# espstack.net
KiCad netlist of a schematic drawn in EAGLE
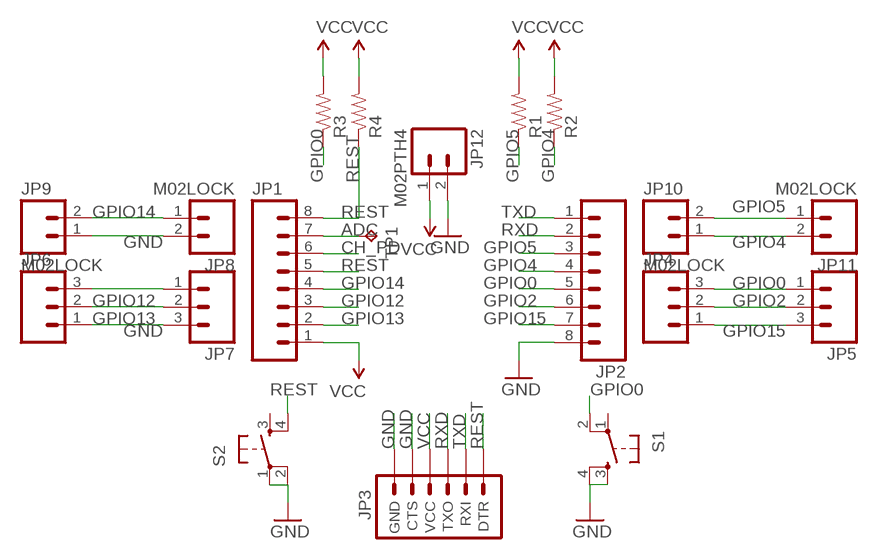
[diagram p0: schematic, sheet 1]

(export (version "E")
  (design (tool "Eeschema 10.0.6"))
  (components
    (comp (ref "JP1")
      (value "M08LOCK_LONGPADS")
      (footprint "eagle-import:1X08_LOCK_LONGPADS")
      (libsource (lib "eagle-import") (part "M08LOCK_LONGPADS"))
    )
    (comp (ref "JP2")
      (value "M08LOCK_LONGPADS")
      (footprint "eagle-import:1X08_LOCK_LONGPADS")
      (libsource (lib "eagle-import") (part "M08LOCK_LONGPADS"))
    )
    (comp (ref "JP3")
      (value "ARDUINO_SERIAL_PROGRAMLOCK")
      (footprint "eagle-import:1X06_LOCK")
      (libsource (lib "eagle-import") (part "ARDUINO_SERIAL_PROGRAMLOCK"))
    )
    (comp (ref "JP4")
      (value "M03LOCK")
      (footprint "eagle-import:1X03_LOCK")
      (libsource (lib "eagle-import") (part "M03LOCK"))
    )
    (comp (ref "JP5")
      (value "M03LOCK")
      (footprint "eagle-import:1X03_LOCK")
      (libsource (lib "eagle-import") (part "M03LOCK"))
    )
    (comp (ref "JP6")
      (value "M03LOCK")
      (footprint "eagle-import:1X03_LOCK")
      (libsource (lib "eagle-import") (part "M03LOCK"))
    )
    (comp (ref "JP7")
      (value "M03LOCK")
      (footprint "eagle-import:1X03_LOCK")
      (libsource (lib "eagle-import") (part "M03LOCK"))
    )
    (comp (ref "JP8")
      (value "M02LOCK")
      (footprint "eagle-import:1X02_LOCK")
      (libsource (lib "eagle-import") (part "M02LOCK"))
    )
    (comp (ref "JP9")
      (value "M02LOCK")
      (footprint "eagle-import:1X02_LOCK")
      (libsource (lib "eagle-import") (part "M02LOCK"))
    )
    (comp (ref "JP10")
      (value "M02LOCK")
      (footprint "eagle-import:1X02_LOCK")
      (libsource (lib "eagle-import") (part "M02LOCK"))
    )
    (comp (ref "JP11")
      (value "M02LOCK")
      (footprint "eagle-import:1X02_LOCK")
      (libsource (lib "eagle-import") (part "M02LOCK"))
    )
    (comp (ref "JP12")
      (value "M02PTH4")
      (footprint "eagle-import:1X02_XTRA_BIG")
      (libsource (lib "eagle-import") (part "M02PTH4"))
    )
    (comp (ref "R1")
      (value "RESISTOR0805-RES")
      (footprint "eagle-import:0805")
      (libsource (lib "eagle-import") (part "RESISTOR0805-RES"))
    )
    (comp (ref "R2")
      (value "RESISTOR0805-RES")
      (footprint "eagle-import:0805")
      (libsource (lib "eagle-import") (part "RESISTOR0805-RES"))
    )
    (comp (ref "R3")
      (value "RESISTOR0805-RES")
      (footprint "eagle-import:0805")
      (libsource (lib "eagle-import") (part "RESISTOR0805-RES"))
    )
    (comp (ref "R4")
      (value "RESISTOR0805-RES")
      (footprint "eagle-import:0805")
      (libsource (lib "eagle-import") (part "RESISTOR0805-RES"))
    )
    (comp (ref "S1")
      (value "TAC_SWITCHPTH")
      (footprint "eagle-import:TACTILE-PTH")
      (libsource (lib "eagle-import") (part "TAC_SWITCHPTH"))
    )
    (comp (ref "S2")
      (value "TAC_SWITCHPTH")
      (footprint "eagle-import:TACTILE-PTH")
      (libsource (lib "eagle-import") (part "TAC_SWITCHPTH"))
    )
    (comp (ref "TP1")
      (value "TPB2,54")
      (footprint "eagle-import:B2,54")
      (libsource (lib "eagle-import") (part "TPB2,54"))
    )
  )
  (nets
    (net (code "1") (name "/ADC") (class "Default")
      (node (ref "JP1") (pin "7") (pinfunction "7_7") (pintype "passive"))
      (node (ref "TP1") (pin "TP") (pinfunction "TP_TP") (pintype "input"))
    )
    (net (code "2") (name "/CH_PD") (class "Default")
      (node (ref "JP1") (pin "6") (pinfunction "6_6") (pintype "passive"))
    )
    (net (code "3") (name "/GPIO0") (class "Default")
      (node (ref "JP2") (pin "5") (pinfunction "5_5") (pintype "passive"))
      (node (ref "JP4") (pin "3") (pinfunction "3_3") (pintype "passive"))
      (node (ref "JP5") (pin "1") (pinfunction "1_1") (pintype "passive"))
      (node (ref "R3") (pin "1") (pinfunction "1_1") (pintype "passive"))
      (node (ref "S1") (pin "2") (pinfunction "2_2") (pintype "passive"))
    )
    (net (code "4") (name "/GPIO2") (class "Default")
      (node (ref "JP2") (pin "6") (pinfunction "6_6") (pintype "passive"))
      (node (ref "JP4") (pin "2") (pinfunction "2_2") (pintype "passive"))
      (node (ref "JP5") (pin "2") (pinfunction "2_2") (pintype "passive"))
    )
    (net (code "5") (name "/GPIO4") (class "Default")
      (node (ref "JP10") (pin "1") (pinfunction "1_1") (pintype "passive"))
      (node (ref "JP11") (pin "2") (pinfunction "2_2") (pintype "passive"))
      (node (ref "JP2") (pin "4") (pinfunction "4_4") (pintype "passive"))
      (node (ref "R2") (pin "1") (pinfunction "1_1") (pintype "passive"))
    )
    (net (code "6") (name "/GPIO5") (class "Default")
      (node (ref "JP10") (pin "2") (pinfunction "2_2") (pintype "passive"))
      (node (ref "JP11") (pin "1") (pinfunction "1_1") (pintype "passive"))
      (node (ref "JP2") (pin "3") (pinfunction "3_3") (pintype "passive"))
      (node (ref "R1") (pin "1") (pinfunction "1_1") (pintype "passive"))
    )
    (net (code "7") (name "/GPIO12") (class "Default")
      (node (ref "JP1") (pin "3") (pinfunction "3_3") (pintype "passive"))
      (node (ref "JP6") (pin "3") (pinfunction "3_3") (pintype "passive"))
      (node (ref "JP7") (pin "1") (pinfunction "1_1") (pintype "passive"))
    )
    (net (code "8") (name "/GPIO13") (class "Default")
      (node (ref "JP1") (pin "2") (pinfunction "2_2") (pintype "passive"))
      (node (ref "JP6") (pin "2") (pinfunction "2_2") (pintype "passive"))
      (node (ref "JP7") (pin "2") (pinfunction "2_2") (pintype "passive"))
    )
    (net (code "9") (name "/GPIO14") (class "Default")
      (node (ref "JP1") (pin "4") (pinfunction "4_4") (pintype "passive"))
      (node (ref "JP8") (pin "1") (pinfunction "1_1") (pintype "passive"))
      (node (ref "JP9") (pin "2") (pinfunction "2_2") (pintype "passive"))
    )
    (net (code "10") (name "/GPIO15") (class "Default")
      (node (ref "JP2") (pin "7") (pinfunction "7_7") (pintype "passive"))
      (node (ref "JP4") (pin "1") (pinfunction "1_1") (pintype "passive"))
      (node (ref "JP5") (pin "3") (pinfunction "3_3") (pintype "passive"))
    )
    (net (code "11") (name "/REST") (class "Default")
      (node (ref "JP1") (pin "5") (pinfunction "5_5") (pintype "passive"))
      (node (ref "JP1") (pin "8") (pinfunction "8_8") (pintype "passive"))
      (node (ref "JP3") (pin "1") (pinfunction "DTR_1") (pintype "passive"))
      (node (ref "R4") (pin "1") (pinfunction "1_1") (pintype "passive"))
      (node (ref "S2") (pin "4") (pinfunction "4_4") (pintype "passive"))
    )
    (net (code "12") (name "/RXD") (class "Default")
      (node (ref "JP2") (pin "2") (pinfunction "2_2") (pintype "passive"))
      (node (ref "JP3") (pin "3") (pinfunction "TXO_3") (pintype "passive"))
    )
    (net (code "13") (name "/TXD") (class "Default")
      (node (ref "JP2") (pin "1") (pinfunction "1_1") (pintype "passive"))
      (node (ref "JP3") (pin "2") (pinfunction "RXI_2") (pintype "passive"))
    )
    (net (code "14") (name "GND") (class "Default")
      (node (ref "JP12") (pin "2") (pinfunction "2_2") (pintype "passive"))
      (node (ref "JP2") (pin "8") (pinfunction "8_8") (pintype "passive"))
      (node (ref "JP3") (pin "5") (pinfunction "CTS_5") (pintype "passive"))
      (node (ref "JP3") (pin "6") (pinfunction "GND_6") (pintype "passive"))
      (node (ref "JP6") (pin "1") (pinfunction "1_1") (pintype "passive"))
      (node (ref "JP7") (pin "3") (pinfunction "3_3") (pintype "passive"))
      (node (ref "JP8") (pin "2") (pinfunction "2_2") (pintype "passive"))
      (node (ref "JP9") (pin "1") (pinfunction "1_1") (pintype "passive"))
      (node (ref "S1") (pin "3") (pinfunction "3_3") (pintype "passive"))
      (node (ref "S1") (pin "4") (pinfunction "4_4") (pintype "passive"))
      (node (ref "S2") (pin "1") (pinfunction "1_1") (pintype "passive"))
      (node (ref "S2") (pin "2") (pinfunction "2_2") (pintype "passive"))
    )
    (net (code "15") (name "VCC") (class "Default")
      (node (ref "JP1") (pin "1") (pinfunction "1_1") (pintype "passive"))
      (node (ref "JP12") (pin "1") (pinfunction "1_1") (pintype "passive"))
      (node (ref "JP3") (pin "4") (pinfunction "VCC_4") (pintype "passive"))
      (node (ref "R1") (pin "2") (pinfunction "2_2") (pintype "passive"))
      (node (ref "R2") (pin "2") (pinfunction "2_2") (pintype "passive"))
      (node (ref "R3") (pin "2") (pinfunction "2_2") (pintype "passive"))
      (node (ref "R4") (pin "2") (pinfunction "2_2") (pintype "passive"))
    )
    (net (code "16") (name "unconnected-(S1-Pad1)") (class "Default")
      (node (ref "S1") (pin "1") (pinfunction "1_1") (pintype "passive"))
    )
    (net (code "17") (name "unconnected-(S2-Pad3)") (class "Default")
      (node (ref "S2") (pin "3") (pinfunction "3_3") (pintype "passive"))
    )
  )
)
